# pogo_adapter_board_v1_1.net
KiCad netlist of a schematic drawn in EAGLE
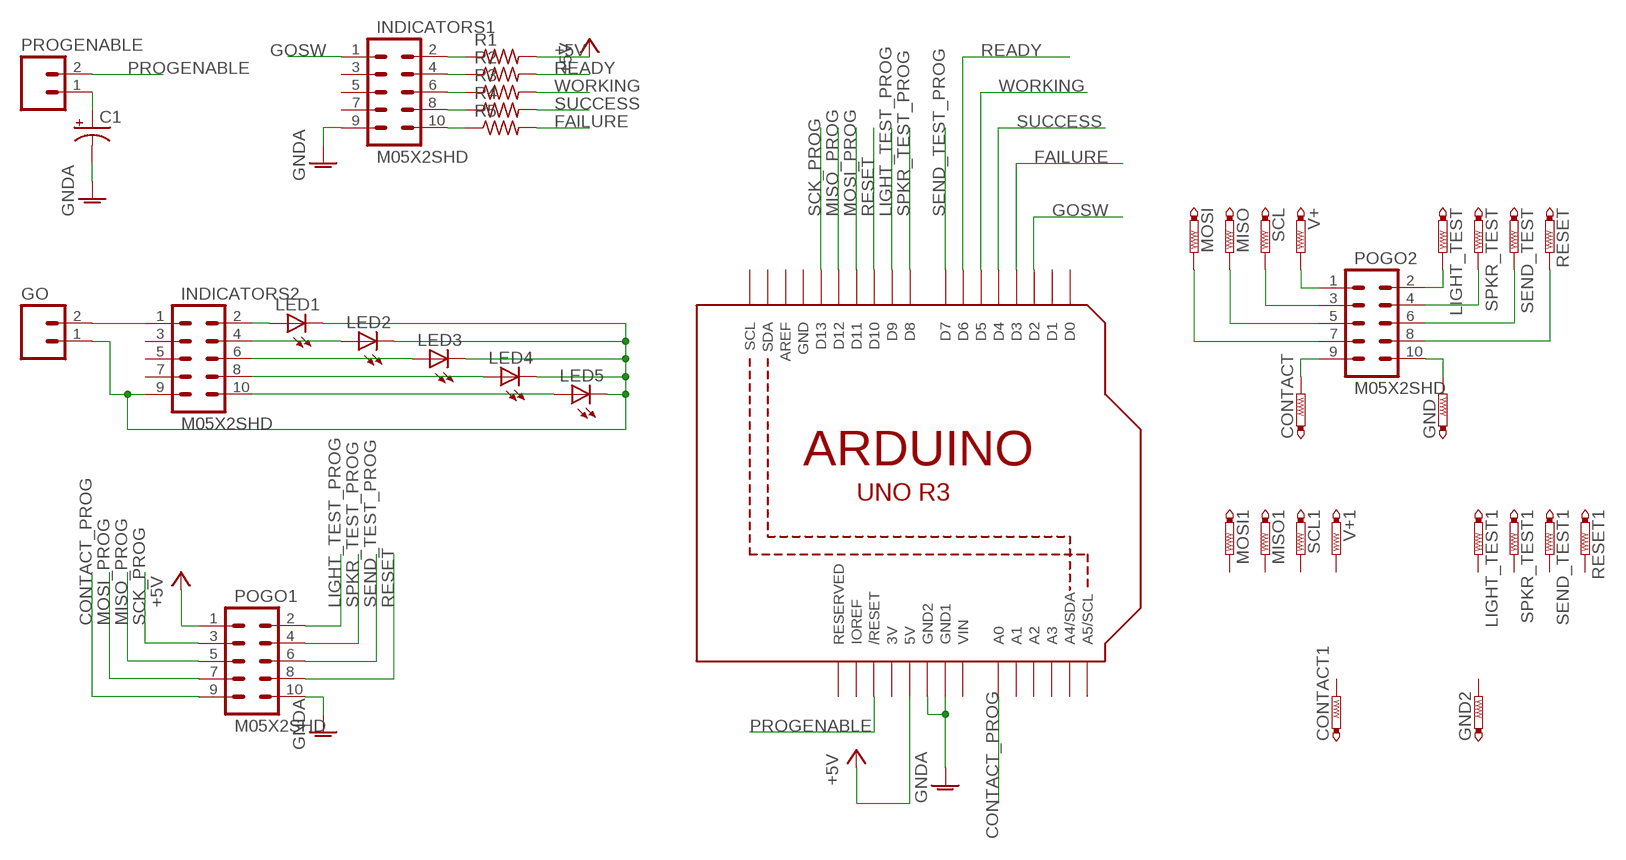
[diagram p0: schematic, sheet 1]

(export (version "E")
  (design (tool "Eeschema 10.0.6"))
  (components
    (comp (ref "C1")
      (value "CAP_POLPTH2")
      (footprint "eagle-import:CPOL-RADIAL-10UF-25V")
      (libsource (lib "eagle-import") (part "CAP_POLPTH2"))
    )
    (comp (ref "CONTACT")
      (value "PTR1PAD1-13")
      (footprint "eagle-import:P1-13")
      (libsource (lib "eagle-import") (part "PTR1PAD1-13"))
    )
    (comp (ref "CONTACT1")
      (value "PTR1PAD1-13")
      (footprint "eagle-import:P1-13")
      (libsource (lib "eagle-import") (part "PTR1PAD1-13"))
    )
    (comp (ref "GND")
      (value "PTR1PAD1-13")
      (footprint "eagle-import:P1-13")
      (libsource (lib "eagle-import") (part "PTR1PAD1-13"))
    )
    (comp (ref "GND2")
      (value "PTR1PAD1-13")
      (footprint "eagle-import:P1-13")
      (libsource (lib "eagle-import") (part "PTR1PAD1-13"))
    )
    (comp (ref "GO")
      (value "M02-JST-2-PTH-NO_SILK")
      (footprint "eagle-import:JST-2-PTH-NS")
      (libsource (lib "eagle-import") (part "M02-JST-2-PTH-NO_SILK"))
    )
    (comp (ref "INDICATORS1")
      (value "M05X2SHD")
      (footprint "eagle-import:2X5-SHROUDED")
      (libsource (lib "eagle-import") (part "M05X2SHD"))
    )
    (comp (ref "INDICATORS2")
      (value "M05X2SHD")
      (footprint "eagle-import:2X5-SHROUDED")
      (libsource (lib "eagle-import") (part "M05X2SHD"))
    )
    (comp (ref "LED1")
      (value "LED10MM")
      (footprint "eagle-import:LED10MM")
      (libsource (lib "eagle-import") (part "LED10MM"))
    )
    (comp (ref "LED2")
      (value "LED10MM")
      (footprint "eagle-import:LED10MM")
      (libsource (lib "eagle-import") (part "LED10MM"))
    )
    (comp (ref "LED3")
      (value "LED10MM")
      (footprint "eagle-import:LED10MM")
      (libsource (lib "eagle-import") (part "LED10MM"))
    )
    (comp (ref "LED4")
      (value "LED10MM")
      (footprint "eagle-import:LED10MM")
      (libsource (lib "eagle-import") (part "LED10MM"))
    )
    (comp (ref "LED5")
      (value "LED10MM")
      (footprint "eagle-import:LED10MM")
      (libsource (lib "eagle-import") (part "LED10MM"))
    )
    (comp (ref "LIGHT_TEST")
      (value "PTR1PAD1-13")
      (footprint "eagle-import:P1-13")
      (libsource (lib "eagle-import") (part "PTR1PAD1-13"))
    )
    (comp (ref "LIGHT_TEST1")
      (value "PTR1PAD1-13")
      (footprint "eagle-import:P1-13")
      (libsource (lib "eagle-import") (part "PTR1PAD1-13"))
    )
    (comp (ref "MISO")
      (value "PTR1PAD1-13")
      (footprint "eagle-import:P1-13")
      (libsource (lib "eagle-import") (part "PTR1PAD1-13"))
    )
    (comp (ref "MISO1")
      (value "PTR1PAD1-13")
      (footprint "eagle-import:P1-13")
      (libsource (lib "eagle-import") (part "PTR1PAD1-13"))
    )
    (comp (ref "MOSI")
      (value "PTR1PAD1-13")
      (footprint "eagle-import:P1-13")
      (libsource (lib "eagle-import") (part "PTR1PAD1-13"))
    )
    (comp (ref "MOSI1")
      (value "PTR1PAD1-13")
      (footprint "eagle-import:P1-13")
      (libsource (lib "eagle-import") (part "PTR1PAD1-13"))
    )
    (comp (ref "POGO1")
      (value "M05X2SHD")
      (footprint "eagle-import:2X5-SHROUDED")
      (libsource (lib "eagle-import") (part "M05X2SHD"))
    )
    (comp (ref "POGO2")
      (value "M05X2SHD")
      (footprint "eagle-import:2X5-SHROUDED")
      (libsource (lib "eagle-import") (part "M05X2SHD"))
    )
    (comp (ref "PROGENABLE")
      (value "M02-JST-2-PTH-NO_SILK")
      (footprint "eagle-import:JST-2-PTH-NS")
      (libsource (lib "eagle-import") (part "M02-JST-2-PTH-NO_SILK"))
    )
    (comp (ref "R1")
      (value "R-US_0204/7")
      (footprint "eagle-import:0204_7")
      (libsource (lib "eagle-import") (part "R-US_0204/7"))
    )
    (comp (ref "R2")
      (value "R-US_0204/7")
      (footprint "eagle-import:0204_7")
      (libsource (lib "eagle-import") (part "R-US_0204/7"))
    )
    (comp (ref "R3")
      (value "R-US_0204/7")
      (footprint "eagle-import:0204_7")
      (libsource (lib "eagle-import") (part "R-US_0204/7"))
    )
    (comp (ref "R4")
      (value "R-US_0204/7")
      (footprint "eagle-import:0204_7")
      (libsource (lib "eagle-import") (part "R-US_0204/7"))
    )
    (comp (ref "R5")
      (value "R-US_0204/7")
      (footprint "eagle-import:0204_7")
      (libsource (lib "eagle-import") (part "R-US_0204/7"))
    )
    (comp (ref "RESET")
      (value "PTR1PAD1-13")
      (footprint "eagle-import:P1-13")
      (libsource (lib "eagle-import") (part "PTR1PAD1-13"))
    )
    (comp (ref "RESET1")
      (value "PTR1PAD1-13")
      (footprint "eagle-import:P1-13")
      (libsource (lib "eagle-import") (part "PTR1PAD1-13"))
    )
    (comp (ref "SCL")
      (value "PTR1PAD1-13")
      (footprint "eagle-import:P1-13")
      (libsource (lib "eagle-import") (part "PTR1PAD1-13"))
    )
    (comp (ref "SCL1")
      (value "PTR1PAD1-13")
      (footprint "eagle-import:P1-13")
      (libsource (lib "eagle-import") (part "PTR1PAD1-13"))
    )
    (comp (ref "SEND_TEST")
      (value "PTR1PAD1-13")
      (footprint "eagle-import:P1-13")
      (libsource (lib "eagle-import") (part "PTR1PAD1-13"))
    )
    (comp (ref "SEND_TEST1")
      (value "PTR1PAD1-13")
      (footprint "eagle-import:P1-13")
      (libsource (lib "eagle-import") (part "PTR1PAD1-13"))
    )
    (comp (ref "SPKR_TEST")
      (value "PTR1PAD1-13")
      (footprint "eagle-import:P1-13")
      (libsource (lib "eagle-import") (part "PTR1PAD1-13"))
    )
    (comp (ref "SPKR_TEST1")
      (value "PTR1PAD1-13")
      (footprint "eagle-import:P1-13")
      (libsource (lib "eagle-import") (part "PTR1PAD1-13"))
    )
    (comp (ref "U1")
      (value "ARDUINOR3")
      (footprint "eagle-import:ARDUINOR3-MINSHIELD")
      (libsource (lib "eagle-import") (part "ARDUINOR3"))
    )
    (comp (ref "V+")
      (value "PTR1PAD1-13")
      (footprint "eagle-import:P1-13")
      (libsource (lib "eagle-import") (part "PTR1PAD1-13"))
    )
    (comp (ref "V+1")
      (value "PTR1PAD1-13")
      (footprint "eagle-import:P1-13")
      (libsource (lib "eagle-import") (part "PTR1PAD1-13"))
    )
  )
  (nets
    (net (code "1") (name "+5V") (class "Default")
      (node (ref "POGO1") (pin "1") (pinfunction "1_1") (pintype "passive"))
      (node (ref "R1") (pin "2") (pinfunction "2_2") (pintype "passive"))
      (node (ref "U1") (pin "5V") (pinfunction "5V_5V") (pintype "power_in"))
    )
    (net (code "2") (name "/3V") (class "Default")
      (node (ref "U1") (pin "3V") (pinfunction "3V_3V") (pintype "power_in"))
    )
    (net (code "3") (name "/CONTACT_PROG") (class "Default")
      (node (ref "POGO1") (pin "9") (pinfunction "9_9") (pintype "passive"))
      (node (ref "U1") (pin "A0") (pinfunction "A0_A0") (pintype "bidirectional"))
    )
    (net (code "4") (name "/FAILURE") (class "Default")
      (node (ref "R5") (pin "2") (pinfunction "2_2") (pintype "passive"))
      (node (ref "U1") (pin "D3") (pinfunction "D3_D3") (pintype "bidirectional"))
    )
    (net (code "5") (name "/GND") (class "Default")
      (node (ref "U1") (pin "GND") (pinfunction "GND_GND") (pintype "power_in"))
    )
    (net (code "6") (name "/GOSW") (class "Default")
      (node (ref "INDICATORS1") (pin "1") (pinfunction "1_1") (pintype "passive"))
      (node (ref "U1") (pin "D2") (pinfunction "D2_D2") (pintype "bidirectional"))
    )
    (net (code "7") (name "/LIGHT_TEST_PROG") (class "Default")
      (node (ref "POGO1") (pin "2") (pinfunction "2_2") (pintype "passive"))
      (node (ref "U1") (pin "D9") (pinfunction "D9_D9") (pintype "bidirectional"))
    )
    (net (code "8") (name "/MISO_PROG") (class "Default")
      (node (ref "POGO1") (pin "5") (pinfunction "5_5") (pintype "passive"))
      (node (ref "U1") (pin "D12") (pinfunction "D12_D12") (pintype "bidirectional"))
    )
    (net (code "9") (name "/MOSI_PROG") (class "Default")
      (node (ref "POGO1") (pin "7") (pinfunction "7_7") (pintype "passive"))
      (node (ref "U1") (pin "D11") (pinfunction "D11_D11") (pintype "bidirectional"))
    )
    (net (code "10") (name "/PROGENABLE") (class "Default")
      (node (ref "PROGENABLE") (pin "2") (pinfunction "2_2") (pintype "passive"))
      (node (ref "U1") (pin "RESET") (pinfunction "/RESET_RESET") (pintype "bidirectional"))
    )
    (net (code "11") (name "/READY") (class "Default")
      (node (ref "R2") (pin "2") (pinfunction "2_2") (pintype "passive"))
      (node (ref "U1") (pin "D6") (pinfunction "D6_D6") (pintype "bidirectional"))
    )
    (net (code "12") (name "/RESET") (class "Default")
      (node (ref "POGO1") (pin "8") (pinfunction "8_8") (pintype "passive"))
      (node (ref "U1") (pin "D10") (pinfunction "D10_D10") (pintype "bidirectional"))
    )
    (net (code "13") (name "/SCK_PROG") (class "Default")
      (node (ref "POGO1") (pin "3") (pinfunction "3_3") (pintype "passive"))
      (node (ref "U1") (pin "D13") (pinfunction "D13_D13") (pintype "bidirectional"))
    )
    (net (code "14") (name "/SEND_TEST_PROG") (class "Default")
      (node (ref "POGO1") (pin "6") (pinfunction "6_6") (pintype "passive"))
      (node (ref "U1") (pin "D7") (pinfunction "D7_D7") (pintype "bidirectional"))
    )
    (net (code "15") (name "/SPKR_TEST_PROG") (class "Default")
      (node (ref "POGO1") (pin "4") (pinfunction "4_4") (pintype "passive"))
      (node (ref "U1") (pin "D8") (pinfunction "D8_D8") (pintype "bidirectional"))
    )
    (net (code "16") (name "/SUCCESS") (class "Default")
      (node (ref "R4") (pin "2") (pinfunction "2_2") (pintype "passive"))
      (node (ref "U1") (pin "D4") (pinfunction "D4_D4") (pintype "bidirectional"))
    )
    (net (code "17") (name "/VIN") (class "Default")
      (node (ref "U1") (pin "VIN") (pinfunction "VIN_VIN") (pintype "power_in"))
    )
    (net (code "18") (name "/WORKING") (class "Default")
      (node (ref "R3") (pin "2") (pinfunction "2_2") (pintype "passive"))
      (node (ref "U1") (pin "D5") (pinfunction "D5_D5") (pintype "bidirectional"))
    )
    (net (code "19") (name "GNDA") (class "Default")
      (node (ref "C1") (pin "2") (pinfunction "-_2") (pintype "passive"))
      (node (ref "INDICATORS1") (pin "9") (pinfunction "9_9") (pintype "passive"))
      (node (ref "POGO1") (pin "10") (pinfunction "10_10") (pintype "passive"))
      (node (ref "U1") (pin "GND1") (pinfunction "GND1_GND1") (pintype "power_in"))
      (node (ref "U1") (pin "GND2") (pinfunction "GND2_GND2") (pintype "power_in"))
    )
    (net (code "20") (name "Net-(C1-+)") (class "Default")
      (node (ref "C1") (pin "1") (pinfunction "+_1") (pintype "passive"))
      (node (ref "PROGENABLE") (pin "1") (pinfunction "1_1") (pintype "passive"))
    )
    (net (code "21") (name "Net-(CONTACT-PadTP)") (class "Default")
      (node (ref "CONTACT") (pin "TP") (pinfunction "TP_TP") (pintype "input"))
      (node (ref "POGO2") (pin "9") (pinfunction "9_9") (pintype "passive"))
    )
    (net (code "22") (name "Net-(GND-PadTP)") (class "Default")
      (node (ref "GND") (pin "TP") (pinfunction "TP_TP") (pintype "input"))
      (node (ref "POGO2") (pin "10") (pinfunction "10_10") (pintype "passive"))
    )
    (net (code "23") (name "Net-(GO-Pad2)") (class "Default")
      (node (ref "GO") (pin "2") (pinfunction "2_2") (pintype "passive"))
      (node (ref "INDICATORS2") (pin "1") (pinfunction "1_1") (pintype "passive"))
    )
    (net (code "24") (name "Net-(INDICATORS1-Pad2)") (class "Default")
      (node (ref "INDICATORS1") (pin "2") (pinfunction "2_2") (pintype "passive"))
      (node (ref "R1") (pin "1") (pinfunction "1_1") (pintype "passive"))
    )
    (net (code "25") (name "Net-(INDICATORS1-Pad4)") (class "Default")
      (node (ref "INDICATORS1") (pin "4") (pinfunction "4_4") (pintype "passive"))
      (node (ref "R2") (pin "1") (pinfunction "1_1") (pintype "passive"))
    )
    (net (code "26") (name "Net-(INDICATORS1-Pad6)") (class "Default")
      (node (ref "INDICATORS1") (pin "6") (pinfunction "6_6") (pintype "passive"))
      (node (ref "R3") (pin "1") (pinfunction "1_1") (pintype "passive"))
    )
    (net (code "27") (name "Net-(INDICATORS1-Pad8)") (class "Default")
      (node (ref "INDICATORS1") (pin "8") (pinfunction "8_8") (pintype "passive"))
      (node (ref "R4") (pin "1") (pinfunction "1_1") (pintype "passive"))
    )
    (net (code "28") (name "Net-(INDICATORS1-Pad10)") (class "Default")
      (node (ref "INDICATORS1") (pin "10") (pinfunction "10_10") (pintype "passive"))
      (node (ref "R5") (pin "1") (pinfunction "1_1") (pintype "passive"))
    )
    (net (code "29") (name "Net-(INDICATORS2-Pad2)") (class "Default")
      (node (ref "INDICATORS2") (pin "2") (pinfunction "2_2") (pintype "passive"))
      (node (ref "LED1") (pin "A") (pinfunction "A_A") (pintype "passive"))
    )
    (net (code "30") (name "Net-(INDICATORS2-Pad4)") (class "Default")
      (node (ref "INDICATORS2") (pin "4") (pinfunction "4_4") (pintype "passive"))
      (node (ref "LED2") (pin "A") (pinfunction "A_A") (pintype "passive"))
    )
    (net (code "31") (name "Net-(INDICATORS2-Pad6)") (class "Default")
      (node (ref "INDICATORS2") (pin "6") (pinfunction "6_6") (pintype "passive"))
      (node (ref "LED3") (pin "A") (pinfunction "A_A") (pintype "passive"))
    )
    (net (code "32") (name "Net-(INDICATORS2-Pad8)") (class "Default")
      (node (ref "INDICATORS2") (pin "8") (pinfunction "8_8") (pintype "passive"))
      (node (ref "LED4") (pin "A") (pinfunction "A_A") (pintype "passive"))
    )
    (net (code "33") (name "Net-(INDICATORS2-Pad10)") (class "Default")
      (node (ref "INDICATORS2") (pin "10") (pinfunction "10_10") (pintype "passive"))
      (node (ref "LED5") (pin "A") (pinfunction "A_A") (pintype "passive"))
    )
    (net (code "34") (name "Net-(LED1-C)") (class "Default")
      (node (ref "GO") (pin "1") (pinfunction "1_1") (pintype "passive"))
      (node (ref "INDICATORS2") (pin "9") (pinfunction "9_9") (pintype "passive"))
      (node (ref "LED1") (pin "K") (pinfunction "C_K") (pintype "passive"))
      (node (ref "LED2") (pin "K") (pinfunction "C_K") (pintype "passive"))
      (node (ref "LED3") (pin "K") (pinfunction "C_K") (pintype "passive"))
      (node (ref "LED4") (pin "K") (pinfunction "C_K") (pintype "passive"))
      (node (ref "LED5") (pin "K") (pinfunction "C_K") (pintype "passive"))
    )
    (net (code "35") (name "Net-(LIGHT_TEST-PadTP)") (class "Default")
      (node (ref "LIGHT_TEST") (pin "TP") (pinfunction "TP_TP") (pintype "input"))
      (node (ref "POGO2") (pin "2") (pinfunction "2_2") (pintype "passive"))
    )
    (net (code "36") (name "Net-(MISO-PadTP)") (class "Default")
      (node (ref "MISO") (pin "TP") (pinfunction "TP_TP") (pintype "input"))
      (node (ref "POGO2") (pin "5") (pinfunction "5_5") (pintype "passive"))
    )
    (net (code "37") (name "Net-(MOSI-PadTP)") (class "Default")
      (node (ref "MOSI") (pin "TP") (pinfunction "TP_TP") (pintype "input"))
      (node (ref "POGO2") (pin "7") (pinfunction "7_7") (pintype "passive"))
    )
    (net (code "38") (name "Net-(POGO2-Pad1)") (class "Default")
      (node (ref "POGO2") (pin "1") (pinfunction "1_1") (pintype "passive"))
      (node (ref "V+") (pin "TP") (pinfunction "TP_TP") (pintype "input"))
    )
    (net (code "39") (name "Net-(POGO2-Pad3)") (class "Default")
      (node (ref "POGO2") (pin "3") (pinfunction "3_3") (pintype "passive"))
      (node (ref "SCL") (pin "TP") (pinfunction "TP_TP") (pintype "input"))
    )
    (net (code "40") (name "Net-(POGO2-Pad4)") (class "Default")
      (node (ref "POGO2") (pin "4") (pinfunction "4_4") (pintype "passive"))
      (node (ref "SPKR_TEST") (pin "TP") (pinfunction "TP_TP") (pintype "input"))
    )
    (net (code "41") (name "Net-(POGO2-Pad6)") (class "Default")
      (node (ref "POGO2") (pin "6") (pinfunction "6_6") (pintype "passive"))
      (node (ref "SEND_TEST") (pin "TP") (pinfunction "TP_TP") (pintype "input"))
    )
    (net (code "42") (name "Net-(POGO2-Pad8)") (class "Default")
      (node (ref "POGO2") (pin "8") (pinfunction "8_8") (pintype "passive"))
      (node (ref "RESET") (pin "TP") (pinfunction "TP_TP") (pintype "input"))
    )
    (net (code "43") (name "unconnected-(CONTACT1-PadTP)") (class "Default")
      (node (ref "CONTACT1") (pin "TP") (pinfunction "TP_TP") (pintype "input"))
    )
    (net (code "44") (name "unconnected-(GND2-PadTP)") (class "Default")
      (node (ref "GND2") (pin "TP") (pinfunction "TP_TP") (pintype "input"))
    )
    (net (code "45") (name "unconnected-(INDICATORS1-Pad3)") (class "Default")
      (node (ref "INDICATORS1") (pin "3") (pinfunction "3_3") (pintype "passive"))
    )
    (net (code "46") (name "unconnected-(INDICATORS1-Pad5)") (class "Default")
      (node (ref "INDICATORS1") (pin "5") (pinfunction "5_5") (pintype "passive"))
    )
    (net (code "47") (name "unconnected-(INDICATORS1-Pad7)") (class "Default")
      (node (ref "INDICATORS1") (pin "7") (pinfunction "7_7") (pintype "passive"))
    )
    (net (code "48") (name "unconnected-(INDICATORS2-Pad3)") (class "Default")
      (node (ref "INDICATORS2") (pin "3") (pinfunction "3_3") (pintype "passive"))
    )
    (net (code "49") (name "unconnected-(INDICATORS2-Pad5)") (class "Default")
      (node (ref "INDICATORS2") (pin "5") (pinfunction "5_5") (pintype "passive"))
    )
    (net (code "50") (name "unconnected-(INDICATORS2-Pad7)") (class "Default")
      (node (ref "INDICATORS2") (pin "7") (pinfunction "7_7") (pintype "passive"))
    )
    (net (code "51") (name "unconnected-(LIGHT_TEST1-PadTP)") (class "Default")
      (node (ref "LIGHT_TEST1") (pin "TP") (pinfunction "TP_TP") (pintype "input"))
    )
    (net (code "52") (name "unconnected-(MISO1-PadTP)") (class "Default")
      (node (ref "MISO1") (pin "TP") (pinfunction "TP_TP") (pintype "input"))
    )
    (net (code "53") (name "unconnected-(MOSI1-PadTP)") (class "Default")
      (node (ref "MOSI1") (pin "TP") (pinfunction "TP_TP") (pintype "input"))
    )
    (net (code "54") (name "unconnected-(RESET1-PadTP)") (class "Default")
      (node (ref "RESET1") (pin "TP") (pinfunction "TP_TP") (pintype "input"))
    )
    (net (code "55") (name "unconnected-(SCL1-PadTP)") (class "Default")
      (node (ref "SCL1") (pin "TP") (pinfunction "TP_TP") (pintype "input"))
    )
    (net (code "56") (name "unconnected-(SEND_TEST1-PadTP)") (class "Default")
      (node (ref "SEND_TEST1") (pin "TP") (pinfunction "TP_TP") (pintype "input"))
    )
    (net (code "57") (name "unconnected-(SPKR_TEST1-PadTP)") (class "Default")
      (node (ref "SPKR_TEST1") (pin "TP") (pinfunction "TP_TP") (pintype "input"))
    )
    (net (code "58") (name "unconnected-(U1-A4{slash}SDA-PadA4)") (class "Default")
      (node (ref "U1") (pin "A4") (pinfunction "A4/SDA_A4") (pintype "bidirectional"))
    )
    (net (code "59") (name "unconnected-(U1-A5{slash}SCL-PadA5)") (class "Default")
      (node (ref "U1") (pin "A5") (pinfunction "A5/SCL_A5") (pintype "bidirectional"))
    )
    (net (code "60") (name "unconnected-(U1-PadA1)") (class "Default")
      (node (ref "U1") (pin "A1") (pinfunction "A1_A1") (pintype "bidirectional"))
    )
    (net (code "61") (name "unconnected-(U1-PadA2)") (class "Default")
      (node (ref "U1") (pin "A2") (pinfunction "A2_A2") (pintype "bidirectional"))
    )
    (net (code "62") (name "unconnected-(U1-PadA3)") (class "Default")
      (node (ref "U1") (pin "A3") (pinfunction "A3_A3") (pintype "bidirectional"))
    )
    (net (code "63") (name "unconnected-(U1-PadAREF)") (class "Default")
      (node (ref "U1") (pin "AREF") (pinfunction "AREF_AREF") (pintype "bidirectional"))
    )
    (net (code "64") (name "unconnected-(U1-PadD0)") (class "Default")
      (node (ref "U1") (pin "D0") (pinfunction "D0_D0") (pintype "bidirectional"))
    )
    (net (code "65") (name "unconnected-(U1-PadD1)") (class "Default")
      (node (ref "U1") (pin "D1") (pinfunction "D1_D1") (pintype "bidirectional"))
    )
    (net (code "66") (name "unconnected-(U1-PadIOREF)") (class "Default")
      (node (ref "U1") (pin "IOREF") (pinfunction "IOREF_IOREF") (pintype "output"))
    )
    (net (code "67") (name "unconnected-(U1-PadRESERVED)") (class "Default")
      (node (ref "U1") (pin "RESERVED") (pinfunction "RESERVED_RESERVED") (pintype "no_connect"))
    )
    (net (code "68") (name "unconnected-(U1-PadSCL)") (class "Default")
      (node (ref "U1") (pin "SCL") (pinfunction "SCL_SCL") (pintype "bidirectional"))
    )
    (net (code "69") (name "unconnected-(U1-PadSDA)") (class "Default")
      (node (ref "U1") (pin "SDA") (pinfunction "SDA_SDA") (pintype "bidirectional"))
    )
    (net (code "70") (name "unconnected-(V+1-PadTP)") (class "Default")
      (node (ref "V+1") (pin "TP") (pinfunction "TP_TP") (pintype "input"))
    )
  )
)
